# Sheet3.net
KiCad netlist of a schematic drawn in Altium Designer
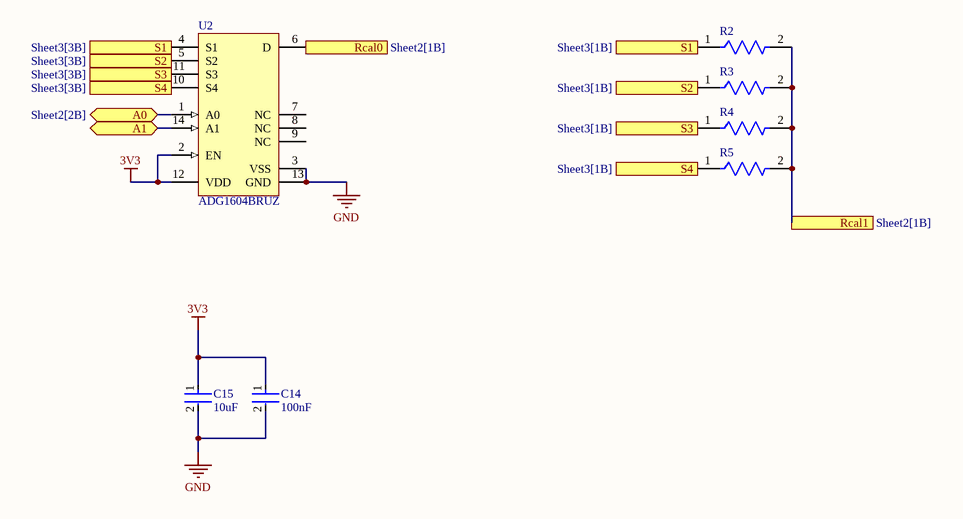
[diagram p0: Sheet3.SchDoc]

(export (version "E")
  (design (tool "Eeschema 10.0.6"))
  (components
    (comp (ref "C14")
      (value "100nF")
      (footprint "FP-GRM18-0_15-MFG")
      (description "CAP CER 10UF 10V X5R 0603")
      (fields
        (field (name "OCTOPART") "https://octopart.com/grm188r61a106ke69d-murata-22851381")
        (field (name "MANUFACTURER PART NUMBER") "GRM188R61A106KE69D")
      )
      (libsource (lib "Altium Content Vault") (part "11868f565c42a9108669ba33697ecf6"))
    )
    (comp (ref "C15")
      (value "10uF")
      (footprint "FP-GRM18-0_15-MFG")
      (fields
        (field (name "OCTOPART") "https://octopart.com/grm188r61a106ke69d-murata-22851381")
        (field (name "MANUFACTURER PART NUMBER") "GRM188R61A106KE69D")
        (field (name "MANUFACTURER") "Murata")
      )
      (libsource (lib "Altium Content Vault") (part "11868f565c42a9108669ba33697ecf6"))
    )
    (comp (ref "R2")
      (value "RT0603BRB07200RL")
      (footprint "FP-RT0603-MFG")
      (description "RES SMD 200 OHM 0.1% 1/10W 0603")
      (fields
        (field (name "OCTOPART") "https://octopart.com/rt0603brb07200rl-yageo-71393466")
        (field (name "MANUFACTURER") "Yageo")
      )
      (libsource (lib "Altium Content Vault") (part "1029c3af85768c4190bb7ad29bc67b5"))
    )
    (comp (ref "R3")
      (value "AC0603FR-132KL")
      (footprint "FP-AC0603-MFG")
      (description "RES 2kΩ 1.00% 0.1W 0603")
      (libsource (lib "Altium Content Vault") (part "1029c3af85768c4190bb7ad29bc67b5"))
    )
    (comp (ref "R4")
      (value "RT0603BRB07200RL")
      (footprint "FP-RT0603-MFG")
      (description "RES SMD 200 OHM 0.1% 1/10W 0603")
      (fields
        (field (name "OCTOPART") "https://octopart.com/rt0603brb07200rl-yageo-71393466")
        (field (name "MANUFACTURER") "Yageo")
      )
      (libsource (lib "Altium Content Vault") (part "1029c3af85768c4190bb7ad29bc67b5"))
    )
    (comp (ref "R5")
      (value "AC0603FR-132KL")
      (footprint "FP-AC0603-MFG")
      (description "RES 2kΩ 1.00% 0.1W 0603")
      (libsource (lib "Altium Content Vault") (part "1029c3af85768c4190bb7ad29bc67b5"))
    )
    (comp (ref "U2")
      (value "ADG1604BRUZ")
      (footprint "ADI-RU-14_N")
      (fields (field (name "MANUFACTURER") "Analog Devices"))
      (libsource (lib "Altium Content Vault") (part "ADI-ADG1604-RU-14"))
    )
  )
  (nets
    (net (code "1") (name "/A0") (class "Default")
      (node (ref "U2") (pin "1") (pinfunction "A0_1") (pintype "input"))
    )
    (net (code "2") (name "/A1") (class "Default")
      (node (ref "U2") (pin "14") (pinfunction "A1_14") (pintype "input"))
    )
    (net (code "3") (name "/Rcal0") (class "Default")
      (node (ref "U2") (pin "6") (pinfunction "D_6") (pintype "passive"))
    )
    (net (code "4") (name "/Rcal1") (class "Default")
      (node (ref "R2") (pin "2") (pinfunction "2_2") (pintype "passive"))
      (node (ref "R3") (pin "2") (pinfunction "2_2") (pintype "passive"))
      (node (ref "R4") (pin "2") (pinfunction "2_2") (pintype "passive"))
      (node (ref "R5") (pin "2") (pinfunction "2_2") (pintype "passive"))
    )
    (net (code "5") (name "/S1") (class "Default")
      (node (ref "R2") (pin "1") (pinfunction "1_1") (pintype "passive"))
      (node (ref "U2") (pin "4") (pinfunction "S1_4") (pintype "passive"))
    )
    (net (code "6") (name "/S2") (class "Default")
      (node (ref "R3") (pin "1") (pinfunction "1_1") (pintype "passive"))
      (node (ref "U2") (pin "5") (pinfunction "S2_5") (pintype "passive"))
    )
    (net (code "7") (name "/S3") (class "Default")
      (node (ref "R4") (pin "1") (pinfunction "1_1") (pintype "passive"))
      (node (ref "U2") (pin "11") (pinfunction "S3_11") (pintype "passive"))
    )
    (net (code "8") (name "/S4") (class "Default")
      (node (ref "R5") (pin "1") (pinfunction "1_1") (pintype "passive"))
      (node (ref "U2") (pin "10") (pinfunction "S4_10") (pintype "passive"))
    )
    (net (code "9") (name "3V3") (class "Default")
      (node (ref "C14") (pin "1") (pinfunction "1_1") (pintype "passive"))
      (node (ref "C15") (pin "1") (pinfunction "1_1") (pintype "passive"))
      (node (ref "U2") (pin "12") (pinfunction "VDD_12") (pintype "power_in"))
      (node (ref "U2") (pin "2") (pinfunction "EN_2") (pintype "input"))
    )
    (net (code "10") (name "GND") (class "Default")
      (node (ref "C14") (pin "2") (pinfunction "2_2") (pintype "passive"))
      (node (ref "C15") (pin "2") (pinfunction "2_2") (pintype "passive"))
      (node (ref "U2") (pin "13") (pinfunction "GND_13") (pintype "power_in"))
      (node (ref "U2") (pin "3") (pinfunction "VSS_3") (pintype "power_in"))
    )
    (net (code "11") (name "unconnected-(U2-NC-Pad7)") (class "Default")
      (node (ref "U2") (pin "7") (pinfunction "NC_7") (pintype "passive"))
    )
    (net (code "12") (name "unconnected-(U2-NC-Pad8)") (class "Default")
      (node (ref "U2") (pin "8") (pinfunction "NC_8") (pintype "passive"))
    )
    (net (code "13") (name "unconnected-(U2-NC-Pad9)") (class "Default")
      (node (ref "U2") (pin "9") (pinfunction "NC_9") (pintype "passive"))
    )
  )
)
